# Greippi_pos_boost.net
KiCad netlist of a schematic drawn in EAGLE
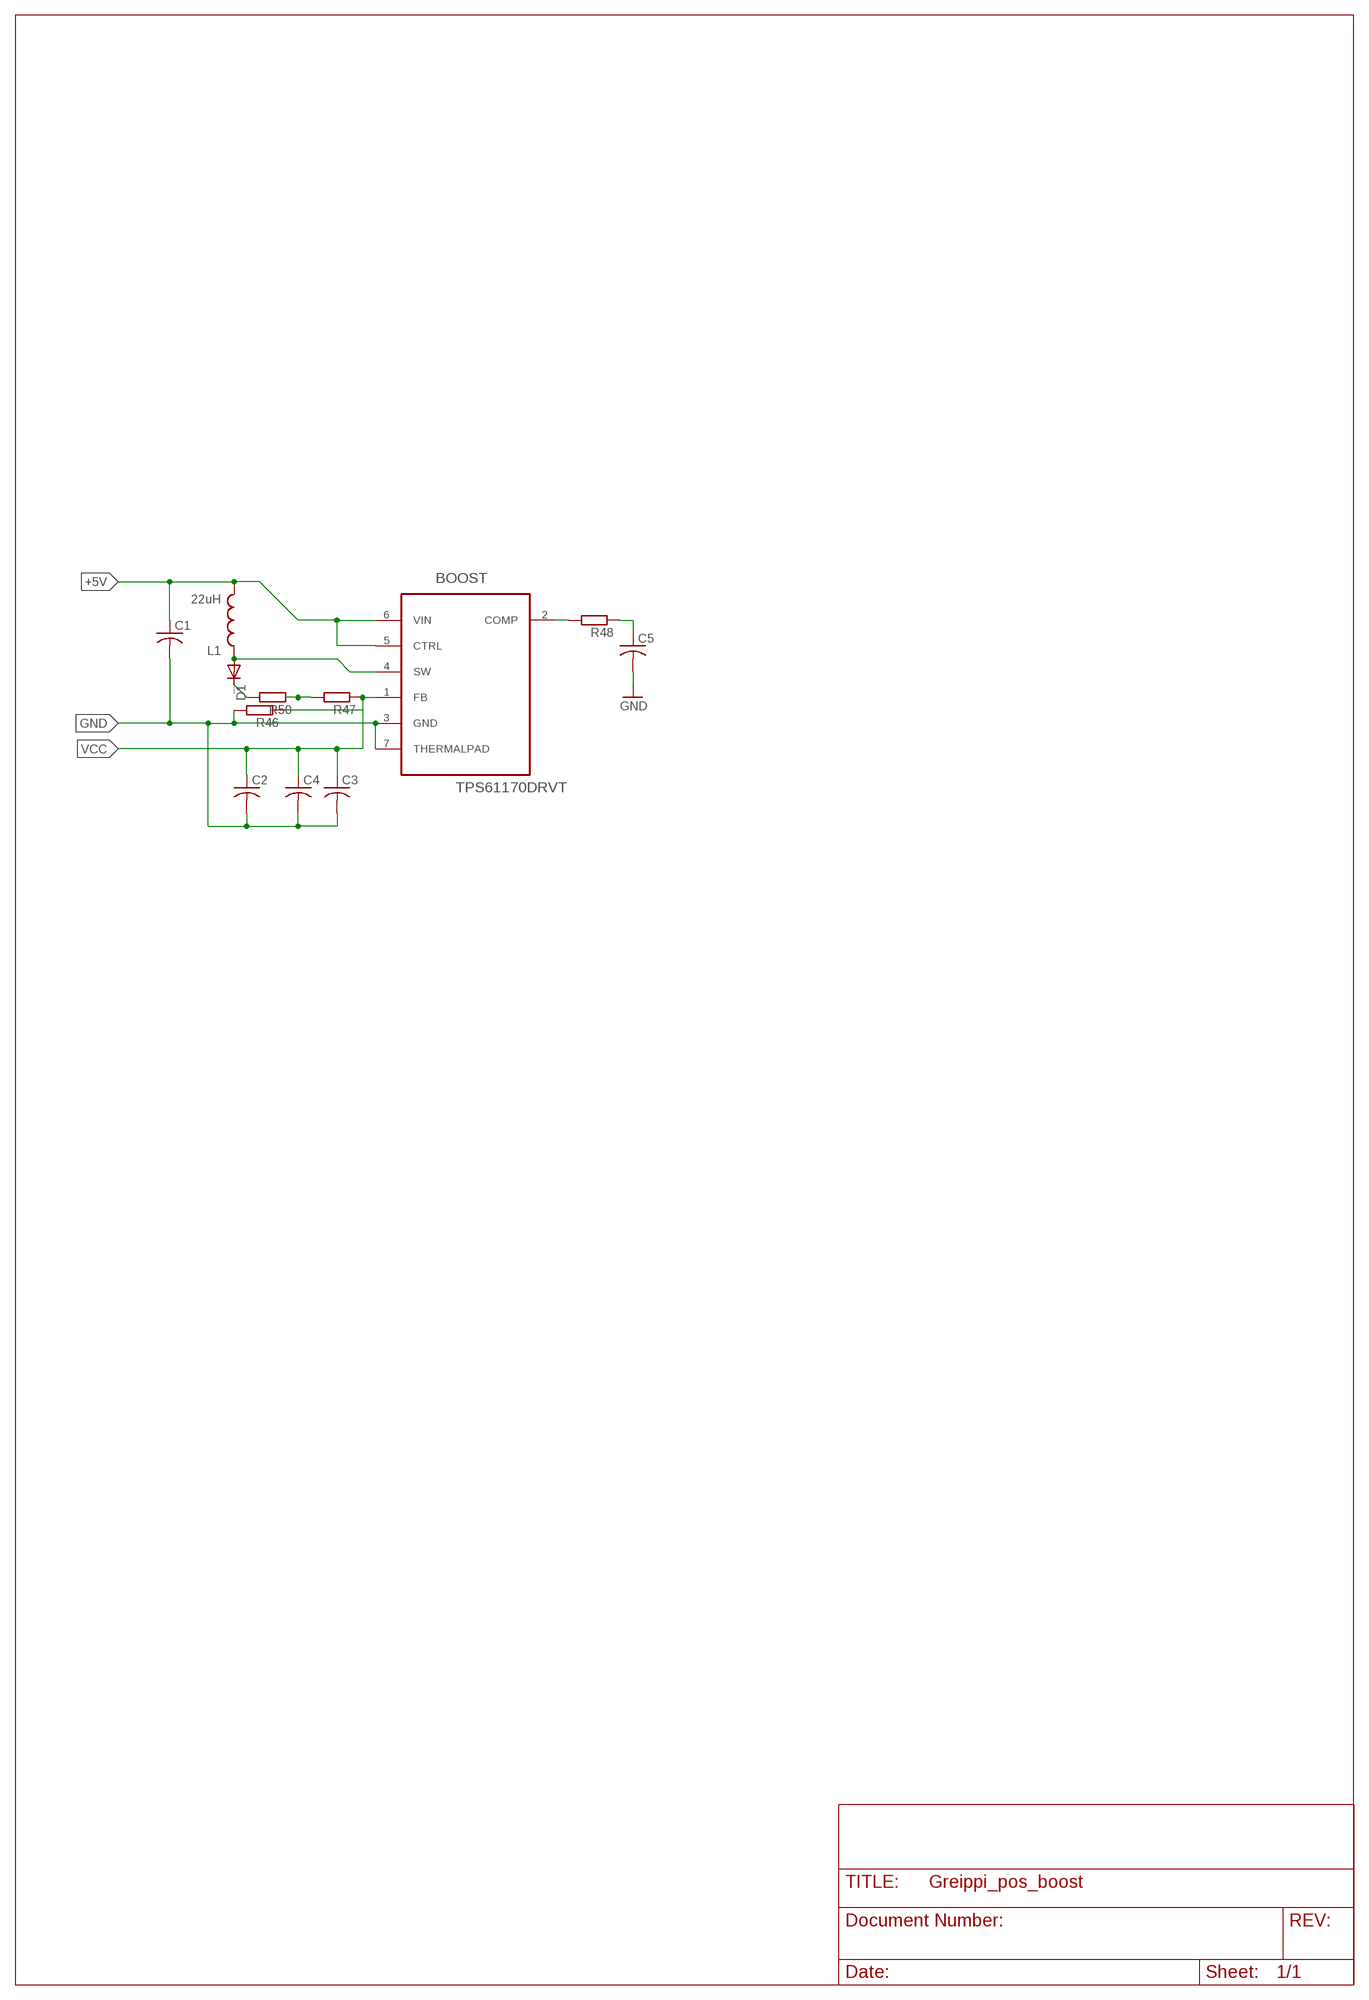
[diagram p0: schematic, sheet 1]

(export (version "E")
  (design (tool "Eeschema 10.0.6"))
  (components
    (comp (ref "BOOST")
      (value "TPS61170DRVT")
      (footprint "eagle-import:SON65P210X210X80-7N")
      (libsource (lib "eagle-import") (part "TPS61170DRVT"))
    )
    (comp (ref "C1")
      (value "C-USC1206")
      (footprint "eagle-import:C1206")
      (libsource (lib "eagle-import") (part "C-USC1206"))
    )
    (comp (ref "C2")
      (value "C-USC0805")
      (footprint "eagle-import:C0805")
      (libsource (lib "eagle-import") (part "C-USC0805"))
    )
    (comp (ref "C3")
      (value "C-USC1206")
      (footprint "eagle-import:C1206")
      (libsource (lib "eagle-import") (part "C-USC1206"))
    )
    (comp (ref "C4")
      (value "C-USC1206")
      (footprint "eagle-import:C1206")
      (libsource (lib "eagle-import") (part "C-USC1206"))
    )
    (comp (ref "C5")
      (value "C-USC1206")
      (footprint "eagle-import:C1206")
      (libsource (lib "eagle-import") (part "C-USC1206"))
    )
    (comp (ref "D1")
      (value "DIODE-SOD123")
      (footprint "eagle-import:SOD123")
      (libsource (lib "eagle-import") (part "DIODE-SOD123"))
    )
    (comp (ref "L1")
      (value "22uH")
      (footprint "eagle-import:SRN6045")
      (libsource (lib "eagle-import") (part "INDUCTORBOURNS_SRN6045"))
    )
    (comp (ref "R46")
      (value "R-EU_R0805")
      (footprint "eagle-import:R0805")
      (libsource (lib "eagle-import") (part "R-EU_R0805"))
    )
    (comp (ref "R47")
      (value "R-EU_R0805")
      (footprint "eagle-import:R0805")
      (libsource (lib "eagle-import") (part "R-EU_R0805"))
    )
    (comp (ref "R48")
      (value "R-EU_R0805")
      (footprint "eagle-import:R0805")
      (libsource (lib "eagle-import") (part "R-EU_R0805"))
    )
    (comp (ref "R50")
      (value "R-EU_R0805")
      (footprint "eagle-import:R0805")
      (libsource (lib "eagle-import") (part "R-EU_R0805"))
    )
  )
  (nets
    (net (code "1") (name "+5V") (class "Default")
      (node (ref "BOOST") (pin "5") (pinfunction "CTRL_5") (pintype "input"))
      (node (ref "BOOST") (pin "6") (pinfunction "VIN_6") (pintype "power_in"))
      (node (ref "C1") (pin "1") (pinfunction "1_1") (pintype "passive"))
      (node (ref "L1") (pin "2") (pinfunction "2_2") (pintype "passive"))
    )
    (net (code "2") (name "GND") (class "Default")
      (node (ref "BOOST") (pin "3") (pinfunction "GND_3") (pintype "passive"))
      (node (ref "BOOST") (pin "7") (pinfunction "THERMALPAD_7") (pintype "passive"))
      (node (ref "C1") (pin "2") (pinfunction "2_2") (pintype "passive"))
      (node (ref "C2") (pin "2") (pinfunction "2_2") (pintype "passive"))
      (node (ref "C3") (pin "2") (pinfunction "2_2") (pintype "passive"))
      (node (ref "C4") (pin "2") (pinfunction "2_2") (pintype "passive"))
      (node (ref "C5") (pin "2") (pinfunction "2_2") (pintype "passive"))
      (node (ref "R46") (pin "2") (pinfunction "2_2") (pintype "passive"))
    )
    (net (code "3") (name "Net-(BOOST-COMP)") (class "Default")
      (node (ref "BOOST") (pin "2") (pinfunction "COMP_2") (pintype "output"))
      (node (ref "R48") (pin "2") (pinfunction "2_2") (pintype "passive"))
    )
    (net (code "4") (name "Net-(BOOST-SW)") (class "Default")
      (node (ref "BOOST") (pin "4") (pinfunction "SW_4") (pintype "input"))
      (node (ref "D1") (pin "A") (pinfunction "A_A") (pintype "passive"))
      (node (ref "L1") (pin "1") (pinfunction "1_1") (pintype "passive"))
    )
    (net (code "5") (name "Net-(C5-Pad1)") (class "Default")
      (node (ref "C5") (pin "1") (pinfunction "1_1") (pintype "passive"))
      (node (ref "R48") (pin "1") (pinfunction "1_1") (pintype "passive"))
    )
    (net (code "6") (name "Net-(D1-PadC)") (class "Default")
      (node (ref "D1") (pin "C") (pinfunction "C_C") (pintype "passive"))
      (node (ref "R50") (pin "2") (pinfunction "2_2") (pintype "passive"))
    )
    (net (code "7") (name "Net-(R47-Pad2)") (class "Default")
      (node (ref "R47") (pin "2") (pinfunction "2_2") (pintype "passive"))
      (node (ref "R50") (pin "1") (pinfunction "1_1") (pintype "passive"))
    )
    (net (code "8") (name "VCC") (class "Default")
      (node (ref "BOOST") (pin "1") (pinfunction "FB_1") (pintype "input"))
      (node (ref "C2") (pin "1") (pinfunction "1_1") (pintype "passive"))
      (node (ref "C3") (pin "1") (pinfunction "1_1") (pintype "passive"))
      (node (ref "C4") (pin "1") (pinfunction "1_1") (pintype "passive"))
      (node (ref "R46") (pin "1") (pinfunction "1_1") (pintype "passive"))
      (node (ref "R47") (pin "1") (pinfunction "1_1") (pintype "passive"))
    )
  )
)
